# RS232.net
KiCad netlist of a schematic drawn in Altium Designer
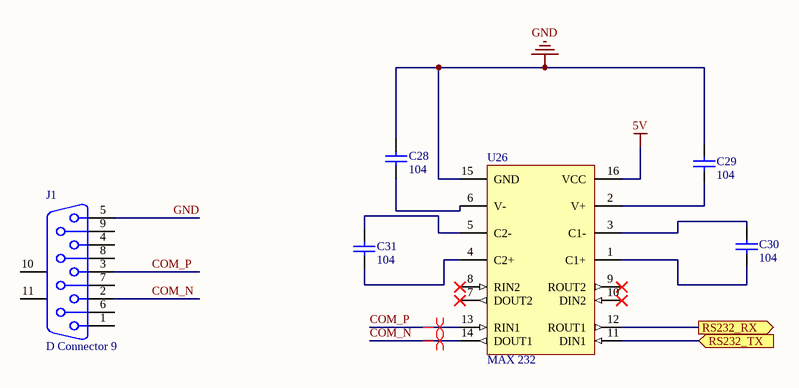
[diagram p0: RS232.SchDoc]

(export (version "E")
  (design (tool "Eeschema 10.0.6"))
  (components
    (comp (ref "C28")
      (value "104")
      (footprint "tu 0805")
      (description "Dán")
      (libsource (lib "Altium_Lib_by_KhueNguyenCreator") (part "Tu 0805 104 50V 10%"))
    )
    (comp (ref "C29")
      (value "104")
      (footprint "tu 0805")
      (description "Dán")
      (libsource (lib "Altium_Lib_by_KhueNguyenCreator") (part "Tu 0805 104 50V 10%"))
    )
    (comp (ref "C30")
      (value "104")
      (footprint "tu 0805")
      (description "Dán")
      (libsource (lib "Altium_Lib_by_KhueNguyenCreator") (part "Tu 0805 104 50V 10%"))
    )
    (comp (ref "C31")
      (value "104")
      (footprint "tu 0805")
      (description "Dán")
      (libsource (lib "Altium_Lib_by_KhueNguyenCreator") (part "Tu 0805 104 50V 10%"))
    )
    (comp (ref "J1")
      (value "D Connector 9")
      (footprint "DSUB1.385-2H9")
      (description "Receptacle Assembly, 9 Position, Right Angle")
      (fields (field (name "PUBLISHER") "Altium Limited"))
      (libsource (lib "BYTECH_HW_LIB_2019 (1)") (part "DB9_RA"))
    )
    (comp (ref "U26")
      (value "MAX 232")
      (footprint "SOIC-16")
      (description "IC DRVR/RCVR MULTCH RS232 16SOIC")
      (fields (field (name "MPN") "MAX3232CDRE4, MAX3232CDR"))
      (libsource (lib "BYTECH_HW_LIB_2019 (1)") (part "MAX3232CDRE4, MAX3232CDR"))
    )
  )
  (nets
    (net (code "1") (name "/COM_N") (class "Default")
      (node (ref "J1") (pin "2") (pinfunction "2_2") (pintype "passive"))
      (node (ref "U26") (pin "14") (pinfunction "DOUT1_14") (pintype "output"))
    )
    (net (code "2") (name "/COM_P") (class "Default")
      (node (ref "J1") (pin "3") (pinfunction "3_3") (pintype "passive"))
      (node (ref "U26") (pin "13") (pinfunction "RIN1_13") (pintype "input"))
    )
    (net (code "3") (name "/RS232_RX") (class "Default")
      (node (ref "U26") (pin "12") (pinfunction "ROUT1_12") (pintype "output"))
    )
    (net (code "4") (name "/RS232_TX") (class "Default")
      (node (ref "U26") (pin "11") (pinfunction "DIN1_11") (pintype "input"))
    )
    (net (code "5") (name "5V") (class "Default")
      (node (ref "U26") (pin "16") (pinfunction "VCC_16") (pintype "power_in"))
    )
    (net (code "6") (name "GND") (class "Default")
      (node (ref "C28") (pin "2") (pinfunction "2_2") (pintype "passive"))
      (node (ref "C29") (pin "2") (pinfunction "2_2") (pintype "passive"))
      (node (ref "J1") (pin "5") (pinfunction "5_5") (pintype "passive"))
      (node (ref "U26") (pin "15") (pinfunction "GND_15") (pintype "power_in"))
    )
    (net (code "7") (name "Net-(U26-C1+)") (class "Default")
      (node (ref "C30") (pin "2") (pinfunction "2_2") (pintype "passive"))
      (node (ref "U26") (pin "1") (pinfunction "C1+_1") (pintype "passive"))
    )
    (net (code "8") (name "Net-(U26-C1-)") (class "Default")
      (node (ref "C30") (pin "1") (pinfunction "1_1") (pintype "passive"))
      (node (ref "U26") (pin "3") (pinfunction "C1-_3") (pintype "passive"))
    )
    (net (code "9") (name "Net-(U26-C2+)") (class "Default")
      (node (ref "C31") (pin "2") (pinfunction "2_2") (pintype "passive"))
      (node (ref "U26") (pin "4") (pinfunction "C2+_4") (pintype "passive"))
    )
    (net (code "10") (name "Net-(U26-C2-)") (class "Default")
      (node (ref "C31") (pin "1") (pinfunction "1_1") (pintype "passive"))
      (node (ref "U26") (pin "5") (pinfunction "C2-_5") (pintype "passive"))
    )
    (net (code "11") (name "Net-(U26-V+)") (class "Default")
      (node (ref "C29") (pin "1") (pinfunction "1_1") (pintype "passive"))
      (node (ref "U26") (pin "2") (pinfunction "V+_2") (pintype "power_in"))
    )
    (net (code "12") (name "Net-(U26-V-)") (class "Default")
      (node (ref "C28") (pin "1") (pinfunction "1_1") (pintype "passive"))
      (node (ref "U26") (pin "6") (pinfunction "V-_6") (pintype "power_in"))
    )
    (net (code "13") (name "unconnected-(J1-MH1-Pad10)") (class "Default")
      (node (ref "J1") (pin "10") (pinfunction "MH1_10") (pintype "passive"))
    )
    (net (code "14") (name "unconnected-(J1-MH2-Pad11)") (class "Default")
      (node (ref "J1") (pin "11") (pinfunction "MH2_11") (pintype "passive"))
    )
    (net (code "15") (name "unconnected-(J1-Pad1)") (class "Default")
      (node (ref "J1") (pin "1") (pinfunction "1_1") (pintype "passive"))
    )
    (net (code "16") (name "unconnected-(J1-Pad4)") (class "Default")
      (node (ref "J1") (pin "4") (pinfunction "4_4") (pintype "passive"))
    )
    (net (code "17") (name "unconnected-(J1-Pad6)") (class "Default")
      (node (ref "J1") (pin "6") (pinfunction "6_6") (pintype "passive"))
    )
    (net (code "18") (name "unconnected-(J1-Pad7)") (class "Default")
      (node (ref "J1") (pin "7") (pinfunction "7_7") (pintype "passive"))
    )
    (net (code "19") (name "unconnected-(J1-Pad8)") (class "Default")
      (node (ref "J1") (pin "8") (pinfunction "8_8") (pintype "passive"))
    )
    (net (code "20") (name "unconnected-(J1-Pad9)") (class "Default")
      (node (ref "J1") (pin "9") (pinfunction "9_9") (pintype "passive"))
    )
    (net (code "21") (name "unconnected-(U26-DIN2-Pad10)") (class "Default")
      (node (ref "U26") (pin "10") (pinfunction "DIN2_10") (pintype "input+no_connect"))
    )
    (net (code "22") (name "unconnected-(U26-DOUT2-Pad7)") (class "Default")
      (node (ref "U26") (pin "7") (pinfunction "DOUT2_7") (pintype "output+no_connect"))
    )
    (net (code "23") (name "unconnected-(U26-RIN2-Pad8)") (class "Default")
      (node (ref "U26") (pin "8") (pinfunction "RIN2_8") (pintype "input+no_connect"))
    )
    (net (code "24") (name "unconnected-(U26-ROUT2-Pad9)") (class "Default")
      (node (ref "U26") (pin "9") (pinfunction "ROUT2_9") (pintype "output+no_connect"))
    )
  )
)
